# IO_Expander.net
KiCad netlist of a schematic drawn in Altium Designer
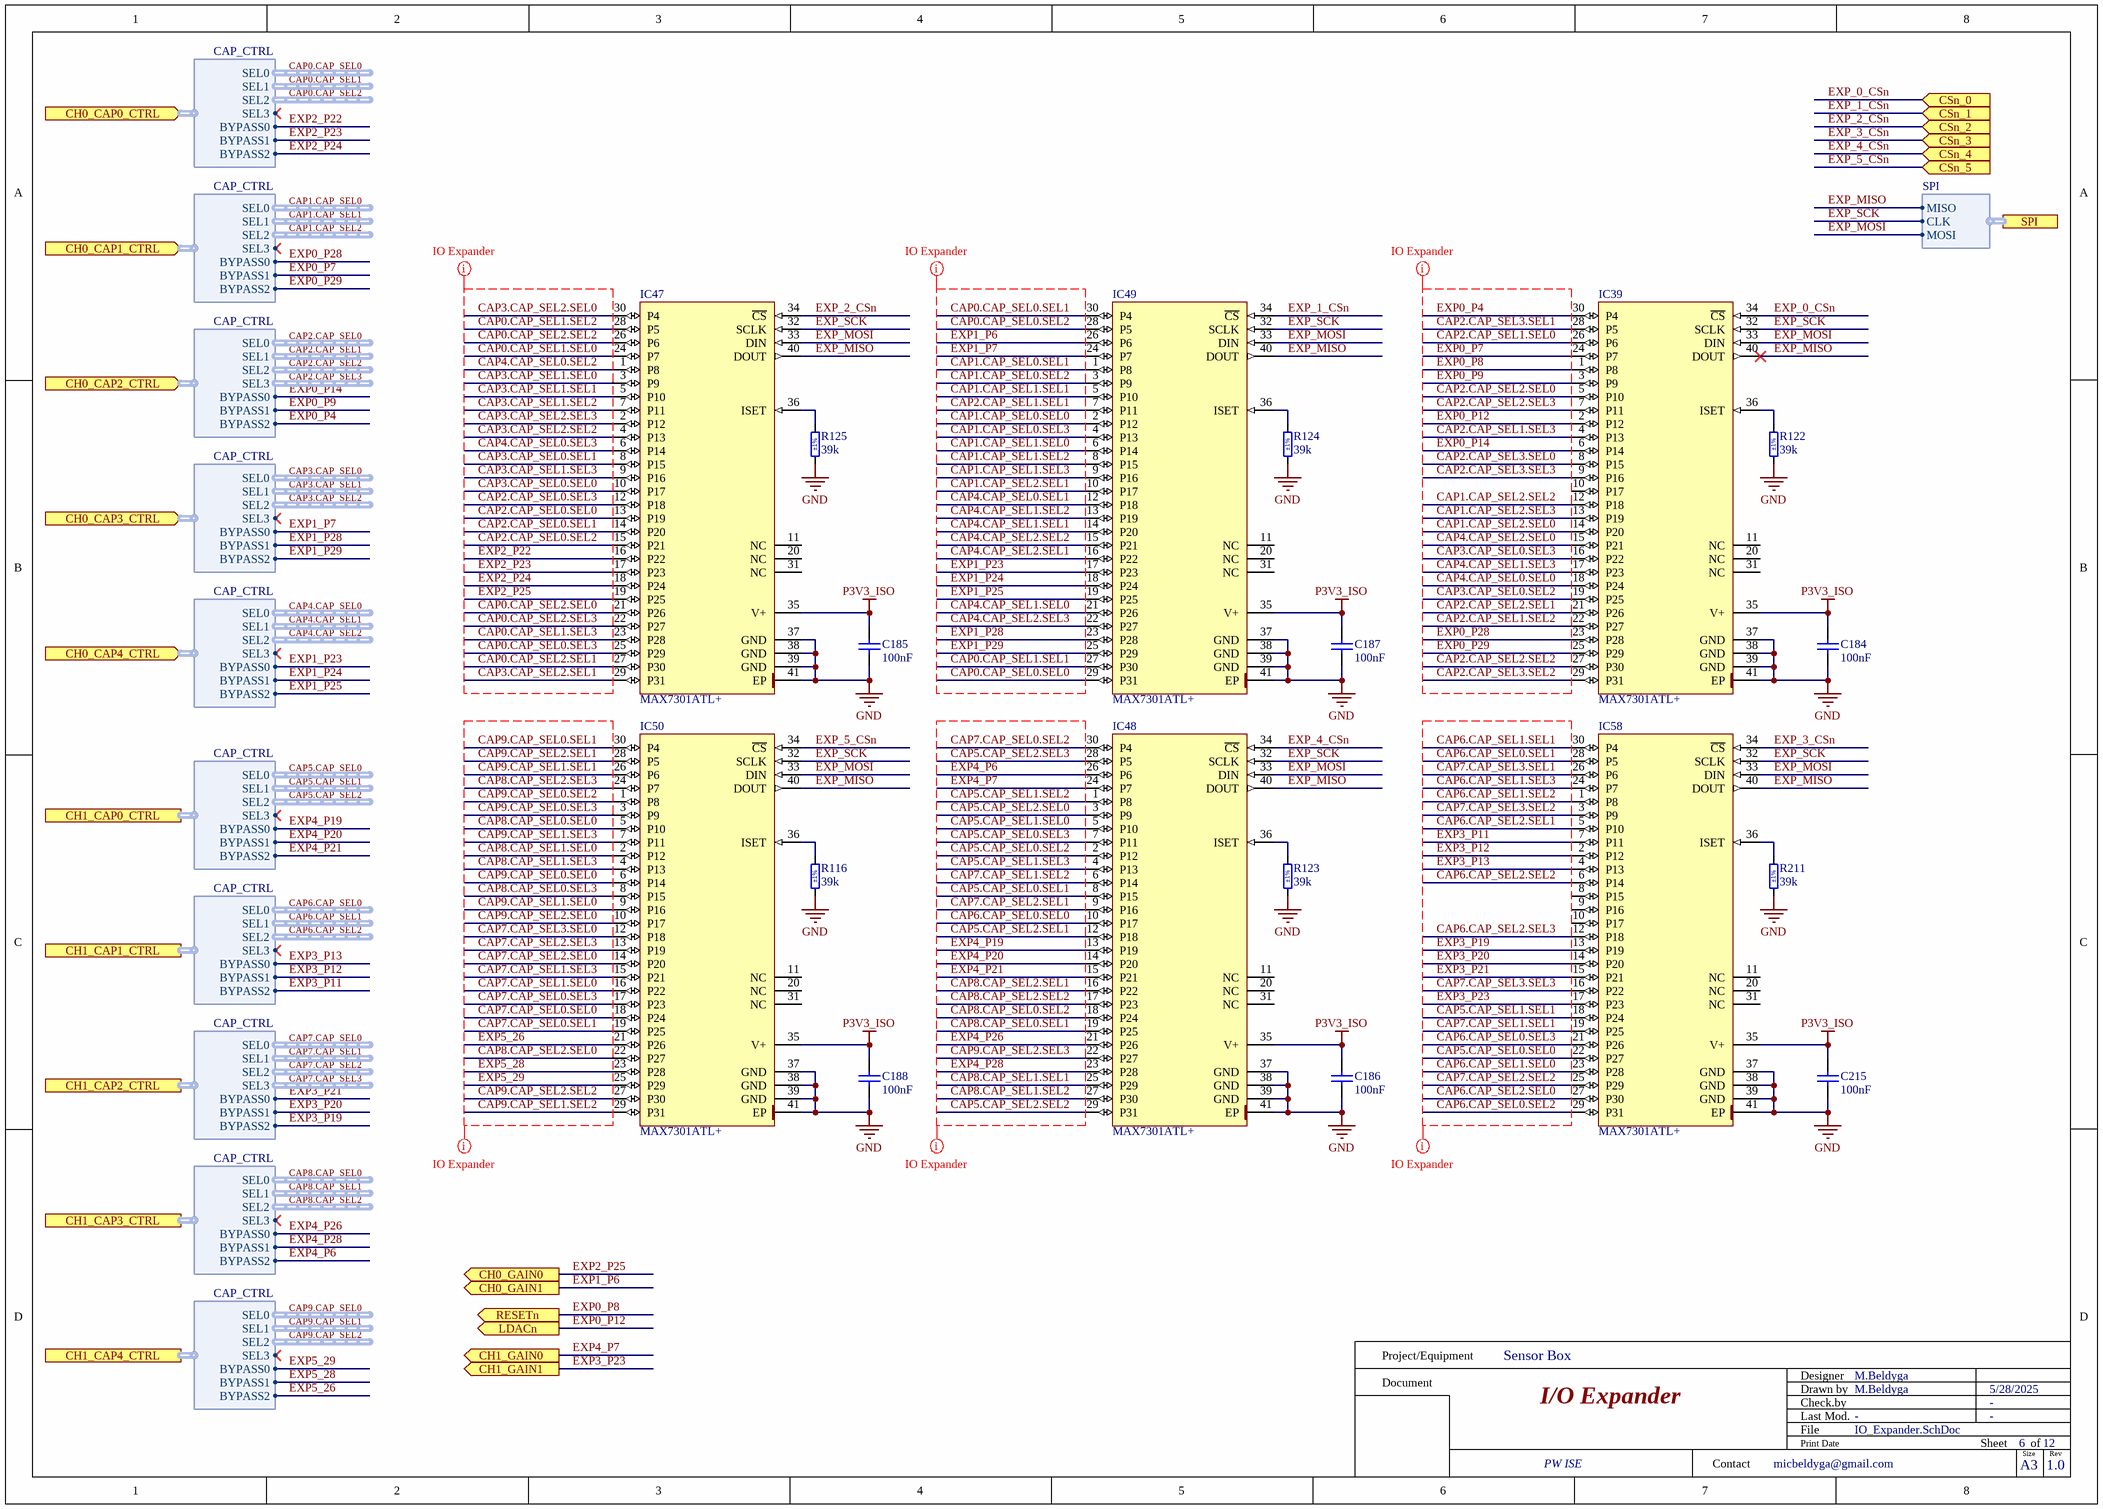
[diagram p0: IO_Expander.SchDoc]

(export (version "E")
  (design (tool "Eeschema 10.0.6"))
  (components
    (comp (ref "C184")
      (value "100nF")
      (footprint "CAPC1005X55N")
      (description "Non-polarised capacitor")
      (fields
        (field (name "PART NUMBER") "CC0402_100NF_50V_10%_X7R")
        (field (name "VOLTAGE") "50V")
        (field (name "AUTHOR") "CERN DEM MR")
      )
      (libsource (lib "Capacitors") (part "Capacitor - non polarized"))
    )
    (comp (ref "C185")
      (value "100nF")
      (footprint "CAPC1005X55N")
      (description "Non-polarised capacitor")
      (fields
        (field (name "PART NUMBER") "CC0402_100NF_50V_10%_X7R")
        (field (name "VOLTAGE") "50V")
        (field (name "AUTHOR") "CERN DEM MR")
      )
      (libsource (lib "Capacitors") (part "Capacitor - non polarized"))
    )
    (comp (ref "C186")
      (value "100nF")
      (footprint "CAPC1005X55N")
      (description "Non-polarised capacitor")
      (fields
        (field (name "PART NUMBER") "CC0402_100NF_50V_10%_X7R")
        (field (name "VOLTAGE") "50V")
        (field (name "AUTHOR") "CERN DEM MR")
      )
      (libsource (lib "Capacitors") (part "Capacitor - non polarized"))
    )
    (comp (ref "C187")
      (value "100nF")
      (footprint "CAPC1005X55N")
      (description "Non-polarised capacitor")
      (fields
        (field (name "PART NUMBER") "CC0402_100NF_50V_10%_X7R")
        (field (name "VOLTAGE") "50V")
        (field (name "AUTHOR") "CERN DEM MR")
      )
      (libsource (lib "Capacitors") (part "Capacitor - non polarized"))
    )
    (comp (ref "C188")
      (value "100nF")
      (footprint "CAPC1005X55N")
      (description "Non-polarised capacitor")
      (fields
        (field (name "PART NUMBER") "CC0402_100NF_50V_10%_X7R")
        (field (name "VOLTAGE") "50V")
        (field (name "AUTHOR") "CERN DEM MR")
      )
      (libsource (lib "Capacitors") (part "Capacitor - non polarized"))
    )
    (comp (ref "C215")
      (value "100nF")
      (footprint "CAPC1005X55N")
      (description "Non-polarised capacitor")
      (fields
        (field (name "PART NUMBER") "CC0402_100NF_50V_10%_X7R")
        (field (name "VOLTAGE") "50V")
        (field (name "AUTHOR") "CERN DEM MR")
      )
      (libsource (lib "Capacitors") (part "Capacitor - non polarized"))
    )
    (comp (ref "IC39")
      (value "MAX7301ATL+")
      (footprint "QFN50P600X600X80-41N-S425")
      (description "4-Wire-Interfaced, 2.5V to 5.5V, 28-Port I/O Expander")
      (fields
        (field (name "MANUFACTURER") "MAXIM")
        (field (name "MANUFACTURER PART NUMBER") "MAX7301ATL")
        (field (name "AUTHOR") "CERN DEM BC")
      )
      (libsource (lib "ICs And Semiconductors") (part "MAX7301ATL+"))
    )
    (comp (ref "IC47")
      (value "MAX7301ATL+")
      (footprint "QFN50P600X600X80-41N-S425")
      (description "4-Wire-Interfaced, 2.5V to 5.5V, 28-Port I/O Expander")
      (fields
        (field (name "MANUFACTURER") "MAXIM")
        (field (name "MANUFACTURER PART NUMBER") "MAX7301ATL")
        (field (name "AUTHOR") "CERN DEM BC")
      )
      (libsource (lib "ICs And Semiconductors") (part "MAX7301ATL+"))
    )
    (comp (ref "IC48")
      (value "MAX7301ATL+")
      (footprint "QFN50P600X600X80-41N-S425")
      (description "4-Wire-Interfaced, 2.5V to 5.5V, 28-Port I/O Expander")
      (fields
        (field (name "MANUFACTURER") "MAXIM")
        (field (name "MANUFACTURER PART NUMBER") "MAX7301ATL")
        (field (name "AUTHOR") "CERN DEM BC")
      )
      (libsource (lib "ICs And Semiconductors") (part "MAX7301ATL+"))
    )
    (comp (ref "IC49")
      (value "MAX7301ATL+")
      (footprint "QFN50P600X600X80-41N-S425")
      (description "4-Wire-Interfaced, 2.5V to 5.5V, 28-Port I/O Expander")
      (fields
        (field (name "MANUFACTURER") "MAXIM")
        (field (name "MANUFACTURER PART NUMBER") "MAX7301ATL")
        (field (name "AUTHOR") "CERN DEM BC")
      )
      (libsource (lib "ICs And Semiconductors") (part "MAX7301ATL+"))
    )
    (comp (ref "IC50")
      (value "MAX7301ATL+")
      (footprint "QFN50P600X600X80-41N-S425")
      (description "4-Wire-Interfaced, 2.5V to 5.5V, 28-Port I/O Expander")
      (fields
        (field (name "MANUFACTURER") "MAXIM")
        (field (name "MANUFACTURER PART NUMBER") "MAX7301ATL")
        (field (name "AUTHOR") "CERN DEM BC")
      )
      (libsource (lib "ICs And Semiconductors") (part "MAX7301ATL+"))
    )
    (comp (ref "IC58")
      (value "MAX7301ATL+")
      (footprint "QFN50P600X600X80-41N-S425")
      (description "4-Wire-Interfaced, 2.5V to 5.5V, 28-Port I/O Expander")
      (fields
        (field (name "MANUFACTURER") "MAXIM")
        (field (name "MANUFACTURER PART NUMBER") "MAX7301ATL")
        (field (name "AUTHOR") "CERN DEM BC")
      )
      (libsource (lib "ICs And Semiconductors") (part "MAX7301ATL+"))
    )
    (comp (ref "R116")
      (value "39k")
      (footprint "RESC1005X40N")
      (description "Resistor - 1%")
      (fields
        (field (name "TOLERANCE") "±1%")
        (field (name "PART NUMBER") "R0402_39K_1%_0.0625W_100PPM")
        (field (name "POWER") "0.0625W")
        (field (name "AUTHOR") "CERN DEM JLC")
      )
      (libsource (lib "Resistors") (part "Resistor - 1%"))
    )
    (comp (ref "R122")
      (value "39k")
      (footprint "RESC1005X40N")
      (description "Resistor - 1%")
      (fields
        (field (name "TOLERANCE") "±1%")
        (field (name "PART NUMBER") "R0402_39K_1%_0.0625W_100PPM")
        (field (name "POWER") "0.0625W")
        (field (name "AUTHOR") "CERN DEM JLC")
      )
      (libsource (lib "Resistors") (part "Resistor - 1%"))
    )
    (comp (ref "R123")
      (value "39k")
      (footprint "RESC1005X40N")
      (description "Resistor - 1%")
      (fields
        (field (name "TOLERANCE") "±1%")
        (field (name "PART NUMBER") "R0402_39K_1%_0.0625W_100PPM")
        (field (name "POWER") "0.0625W")
        (field (name "AUTHOR") "CERN DEM JLC")
      )
      (libsource (lib "Resistors") (part "Resistor - 1%"))
    )
    (comp (ref "R124")
      (value "39k")
      (footprint "RESC1005X40N")
      (description "Resistor - 1%")
      (fields
        (field (name "TOLERANCE") "±1%")
        (field (name "PART NUMBER") "R0402_39K_1%_0.0625W_100PPM")
        (field (name "POWER") "0.0625W")
        (field (name "AUTHOR") "CERN DEM JLC")
      )
      (libsource (lib "Resistors") (part "Resistor - 1%"))
    )
    (comp (ref "R125")
      (value "39k")
      (footprint "RESC1005X40N")
      (description "Resistor - 1%")
      (fields
        (field (name "TOLERANCE") "±1%")
        (field (name "PART NUMBER") "R0402_39K_1%_0.0625W_100PPM")
        (field (name "POWER") "0.0625W")
        (field (name "AUTHOR") "CERN DEM JLC")
      )
      (libsource (lib "Resistors") (part "Resistor - 1%"))
    )
    (comp (ref "R211")
      (value "39k")
      (footprint "RESC1005X40N")
      (description "Resistor - 1%")
      (fields
        (field (name "TOLERANCE") "±1%")
        (field (name "PART NUMBER") "R0402_39K_1%_0.0625W_100PPM")
        (field (name "POWER") "0.0625W")
        (field (name "AUTHOR") "CERN DEM JLC")
      )
      (libsource (lib "Resistors") (part "Resistor - 1%"))
    )
  )
  (nets
    (net (code "39") (name "/CAP0.CAP_SEL0.SEL0") (class "Default")
      (node (ref "IC49") (pin "29") (pinfunction "P31_29") (pintype "bidirectional"))
    )
    (net (code "40") (name "/CAP0.CAP_SEL0.SEL1") (class "Default")
      (node (ref "IC49") (pin "30") (pinfunction "P4_30") (pintype "bidirectional"))
    )
    (net (code "41") (name "/CAP0.CAP_SEL0.SEL2") (class "Default")
      (node (ref "IC49") (pin "28") (pinfunction "P5_28") (pintype "bidirectional"))
    )
    (net (code "42") (name "/CAP0.CAP_SEL0.SEL3") (class "Default")
      (node (ref "IC47") (pin "25") (pinfunction "P29_25") (pintype "bidirectional"))
    )
    (net (code "43") (name "/CAP0.CAP_SEL1.SEL0") (class "Default")
      (node (ref "IC47") (pin "24") (pinfunction "P7_24") (pintype "bidirectional"))
    )
    (net (code "44") (name "/CAP0.CAP_SEL1.SEL1") (class "Default")
      (node (ref "IC49") (pin "27") (pinfunction "P30_27") (pintype "bidirectional"))
    )
    (net (code "45") (name "/CAP0.CAP_SEL1.SEL2") (class "Default")
      (node (ref "IC47") (pin "28") (pinfunction "P5_28") (pintype "bidirectional"))
    )
    (net (code "46") (name "/CAP0.CAP_SEL1.SEL3") (class "Default")
      (node (ref "IC47") (pin "23") (pinfunction "P28_23") (pintype "bidirectional"))
    )
    (net (code "47") (name "/CAP0.CAP_SEL2.SEL0") (class "Default")
      (node (ref "IC47") (pin "21") (pinfunction "P26_21") (pintype "bidirectional"))
    )
    (net (code "48") (name "/CAP0.CAP_SEL2.SEL1") (class "Default")
      (node (ref "IC47") (pin "27") (pinfunction "P30_27") (pintype "bidirectional"))
    )
    (net (code "49") (name "/CAP0.CAP_SEL2.SEL2") (class "Default")
      (node (ref "IC47") (pin "26") (pinfunction "P6_26") (pintype "bidirectional"))
    )
    (net (code "50") (name "/CAP0.CAP_SEL2.SEL3") (class "Default")
      (node (ref "IC47") (pin "22") (pinfunction "P27_22") (pintype "bidirectional"))
    )
    (net (code "51") (name "/CAP1.CAP_SEL0.SEL0") (class "Default")
      (node (ref "IC49") (pin "2") (pinfunction "P12_2") (pintype "bidirectional"))
    )
    (net (code "52") (name "/CAP1.CAP_SEL0.SEL1") (class "Default")
      (node (ref "IC49") (pin "1") (pinfunction "P8_1") (pintype "bidirectional"))
    )
    (net (code "53") (name "/CAP1.CAP_SEL0.SEL2") (class "Default")
      (node (ref "IC49") (pin "3") (pinfunction "P9_3") (pintype "bidirectional"))
    )
    (net (code "54") (name "/CAP1.CAP_SEL0.SEL3") (class "Default")
      (node (ref "IC49") (pin "4") (pinfunction "P13_4") (pintype "bidirectional"))
    )
    (net (code "55") (name "/CAP1.CAP_SEL1.SEL0") (class "Default")
      (node (ref "IC49") (pin "6") (pinfunction "P14_6") (pintype "bidirectional"))
    )
    (net (code "56") (name "/CAP1.CAP_SEL1.SEL1") (class "Default")
      (node (ref "IC49") (pin "5") (pinfunction "P10_5") (pintype "bidirectional"))
    )
    (net (code "57") (name "/CAP1.CAP_SEL1.SEL2") (class "Default")
      (node (ref "IC49") (pin "8") (pinfunction "P15_8") (pintype "bidirectional"))
    )
    (net (code "58") (name "/CAP1.CAP_SEL1.SEL3") (class "Default")
      (node (ref "IC49") (pin "9") (pinfunction "P16_9") (pintype "bidirectional"))
    )
    (net (code "59") (name "/CAP1.CAP_SEL2.SEL0") (class "Default")
      (node (ref "IC39") (pin "14") (pinfunction "P20_14") (pintype "bidirectional"))
    )
    (net (code "60") (name "/CAP1.CAP_SEL2.SEL1") (class "Default")
      (node (ref "IC49") (pin "10") (pinfunction "P17_10") (pintype "bidirectional"))
    )
    (net (code "61") (name "/CAP1.CAP_SEL2.SEL2") (class "Default")
      (node (ref "IC39") (pin "12") (pinfunction "P18_12") (pintype "bidirectional"))
    )
    (net (code "62") (name "/CAP1.CAP_SEL2.SEL3") (class "Default")
      (node (ref "IC39") (pin "13") (pinfunction "P19_13") (pintype "bidirectional"))
    )
    (net (code "63") (name "/CAP2.CAP_SEL0.SEL0") (class "Default")
      (node (ref "IC47") (pin "13") (pinfunction "P19_13") (pintype "bidirectional"))
    )
    (net (code "64") (name "/CAP2.CAP_SEL0.SEL1") (class "Default")
      (node (ref "IC47") (pin "14") (pinfunction "P20_14") (pintype "bidirectional"))
    )
    (net (code "65") (name "/CAP2.CAP_SEL0.SEL2") (class "Default")
      (node (ref "IC47") (pin "15") (pinfunction "P21_15") (pintype "bidirectional"))
    )
    (net (code "66") (name "/CAP2.CAP_SEL0.SEL3") (class "Default")
      (node (ref "IC47") (pin "12") (pinfunction "P18_12") (pintype "bidirectional"))
    )
    (net (code "67") (name "/CAP2.CAP_SEL1.SEL0") (class "Default")
      (node (ref "IC39") (pin "26") (pinfunction "P6_26") (pintype "bidirectional"))
    )
    (net (code "68") (name "/CAP2.CAP_SEL1.SEL1") (class "Default")
      (node (ref "IC49") (pin "7") (pinfunction "P11_7") (pintype "bidirectional"))
    )
    (net (code "69") (name "/CAP2.CAP_SEL1.SEL2") (class "Default")
      (node (ref "IC39") (pin "22") (pinfunction "P27_22") (pintype "bidirectional"))
    )
    (net (code "70") (name "/CAP2.CAP_SEL1.SEL3") (class "Default")
      (node (ref "IC39") (pin "4") (pinfunction "P13_4") (pintype "bidirectional"))
    )
    (net (code "71") (name "/CAP2.CAP_SEL2.SEL0") (class "Default")
      (node (ref "IC39") (pin "5") (pinfunction "P10_5") (pintype "bidirectional"))
    )
    (net (code "72") (name "/CAP2.CAP_SEL2.SEL1") (class "Default")
      (node (ref "IC39") (pin "21") (pinfunction "P26_21") (pintype "bidirectional"))
    )
    (net (code "73") (name "/CAP2.CAP_SEL2.SEL2") (class "Default")
      (node (ref "IC39") (pin "27") (pinfunction "P30_27") (pintype "bidirectional"))
    )
    (net (code "74") (name "/CAP2.CAP_SEL2.SEL3") (class "Default")
      (node (ref "IC39") (pin "7") (pinfunction "P11_7") (pintype "bidirectional"))
    )
    (net (code "75") (name "/CAP2.CAP_SEL3.SEL0") (class "Default")
      (node (ref "IC39") (pin "8") (pinfunction "P15_8") (pintype "bidirectional"))
    )
    (net (code "76") (name "/CAP2.CAP_SEL3.SEL1") (class "Default")
      (node (ref "IC39") (pin "28") (pinfunction "P5_28") (pintype "bidirectional"))
    )
    (net (code "77") (name "/CAP2.CAP_SEL3.SEL2") (class "Default")
      (node (ref "IC39") (pin "29") (pinfunction "P31_29") (pintype "bidirectional"))
    )
    (net (code "78") (name "/CAP2.CAP_SEL3.SEL3") (class "Default")
      (node (ref "IC39") (pin "9") (pinfunction "P16_9") (pintype "bidirectional"))
    )
    (net (code "80") (name "/CAP3.CAP_SEL0.SEL0") (class "Default")
      (node (ref "IC47") (pin "10") (pinfunction "P17_10") (pintype "bidirectional"))
    )
    (net (code "81") (name "/CAP3.CAP_SEL0.SEL1") (class "Default")
      (node (ref "IC47") (pin "8") (pinfunction "P15_8") (pintype "bidirectional"))
    )
    (net (code "82") (name "/CAP3.CAP_SEL0.SEL2") (class "Default")
      (node (ref "IC39") (pin "19") (pinfunction "P25_19") (pintype "bidirectional"))
    )
    (net (code "83") (name "/CAP3.CAP_SEL0.SEL3") (class "Default")
      (node (ref "IC39") (pin "16") (pinfunction "P22_16") (pintype "bidirectional"))
    )
    (net (code "84") (name "/CAP3.CAP_SEL1.SEL0") (class "Default")
      (node (ref "IC47") (pin "3") (pinfunction "P9_3") (pintype "bidirectional"))
    )
    (net (code "85") (name "/CAP3.CAP_SEL1.SEL1") (class "Default")
      (node (ref "IC47") (pin "5") (pinfunction "P10_5") (pintype "bidirectional"))
    )
    (net (code "86") (name "/CAP3.CAP_SEL1.SEL2") (class "Default")
      (node (ref "IC47") (pin "7") (pinfunction "P11_7") (pintype "bidirectional"))
    )
    (net (code "87") (name "/CAP3.CAP_SEL1.SEL3") (class "Default")
      (node (ref "IC47") (pin "9") (pinfunction "P16_9") (pintype "bidirectional"))
    )
    (net (code "88") (name "/CAP3.CAP_SEL2.SEL0") (class "Default")
      (node (ref "IC47") (pin "30") (pinfunction "P4_30") (pintype "bidirectional"))
    )
    (net (code "89") (name "/CAP3.CAP_SEL2.SEL1") (class "Default")
      (node (ref "IC47") (pin "29") (pinfunction "P31_29") (pintype "bidirectional"))
    )
    (net (code "90") (name "/CAP3.CAP_SEL2.SEL2") (class "Default")
      (node (ref "IC47") (pin "4") (pinfunction "P13_4") (pintype "bidirectional"))
    )
    (net (code "91") (name "/CAP3.CAP_SEL2.SEL3") (class "Default")
      (node (ref "IC47") (pin "2") (pinfunction "P12_2") (pintype "bidirectional"))
    )
    (net (code "92") (name "/CAP4.CAP_SEL0.SEL0") (class "Default")
      (node (ref "IC39") (pin "18") (pinfunction "P24_18") (pintype "bidirectional"))
    )
    (net (code "93") (name "/CAP4.CAP_SEL0.SEL1") (class "Default")
      (node (ref "IC49") (pin "12") (pinfunction "P18_12") (pintype "bidirectional"))
    )
    (net (code "94") (name "/CAP4.CAP_SEL0.SEL2") (class "Default")
      (node (ref "IC47") (pin "1") (pinfunction "P8_1") (pintype "bidirectional"))
    )
    (net (code "95") (name "/CAP4.CAP_SEL0.SEL3") (class "Default")
      (node (ref "IC47") (pin "6") (pinfunction "P14_6") (pintype "bidirectional"))
    )
    (net (code "96") (name "/CAP4.CAP_SEL1.SEL0") (class "Default")
      (node (ref "IC49") (pin "21") (pinfunction "P26_21") (pintype "bidirectional"))
    )
    (net (code "97") (name "/CAP4.CAP_SEL1.SEL1") (class "Default")
      (node (ref "IC49") (pin "14") (pinfunction "P20_14") (pintype "bidirectional"))
    )
    (net (code "98") (name "/CAP4.CAP_SEL1.SEL2") (class "Default")
      (node (ref "IC49") (pin "13") (pinfunction "P19_13") (pintype "bidirectional"))
    )
    (net (code "99") (name "/CAP4.CAP_SEL1.SEL3") (class "Default")
      (node (ref "IC39") (pin "17") (pinfunction "P23_17") (pintype "bidirectional"))
    )
    (net (code "100") (name "/CAP4.CAP_SEL2.SEL0") (class "Default")
      (node (ref "IC39") (pin "15") (pinfunction "P21_15") (pintype "bidirectional"))
    )
    (net (code "101") (name "/CAP4.CAP_SEL2.SEL1") (class "Default")
      (node (ref "IC49") (pin "16") (pinfunction "P22_16") (pintype "bidirectional"))
    )
    (net (code "102") (name "/CAP4.CAP_SEL2.SEL2") (class "Default")
      (node (ref "IC49") (pin "15") (pinfunction "P21_15") (pintype "bidirectional"))
    )
    (net (code "103") (name "/CAP4.CAP_SEL2.SEL3") (class "Default")
      (node (ref "IC49") (pin "22") (pinfunction "P27_22") (pintype "bidirectional"))
    )
    (net (code "104") (name "/CAP5.CAP_SEL0.SEL0") (class "Default")
      (node (ref "IC58") (pin "22") (pinfunction "P27_22") (pintype "bidirectional"))
    )
    (net (code "105") (name "/CAP5.CAP_SEL0.SEL1") (class "Default")
      (node (ref "IC48") (pin "8") (pinfunction "P15_8") (pintype "bidirectional"))
    )
    (net (code "106") (name "/CAP5.CAP_SEL0.SEL2") (class "Default")
      (node (ref "IC48") (pin "2") (pinfunction "P12_2") (pintype "bidirectional"))
    )
    (net (code "107") (name "/CAP5.CAP_SEL0.SEL3") (class "Default")
      (node (ref "IC48") (pin "7") (pinfunction "P11_7") (pintype "bidirectional"))
    )
    (net (code "108") (name "/CAP5.CAP_SEL1.SEL0") (class "Default")
      (node (ref "IC48") (pin "5") (pinfunction "P10_5") (pintype "bidirectional"))
    )
    (net (code "109") (name "/CAP5.CAP_SEL1.SEL1") (class "Default")
      (node (ref "IC58") (pin "18") (pinfunction "P24_18") (pintype "bidirectional"))
    )
    (net (code "110") (name "/CAP5.CAP_SEL1.SEL2") (class "Default")
      (node (ref "IC48") (pin "1") (pinfunction "P8_1") (pintype "bidirectional"))
    )
    (net (code "111") (name "/CAP5.CAP_SEL1.SEL3") (class "Default")
      (node (ref "IC48") (pin "4") (pinfunction "P13_4") (pintype "bidirectional"))
    )
    (net (code "112") (name "/CAP5.CAP_SEL2.SEL0") (class "Default")
      (node (ref "IC48") (pin "3") (pinfunction "P9_3") (pintype "bidirectional"))
    )
    (net (code "113") (name "/CAP5.CAP_SEL2.SEL1") (class "Default")
      (node (ref "IC48") (pin "12") (pinfunction "P18_12") (pintype "bidirectional"))
    )
    (net (code "114") (name "/CAP5.CAP_SEL2.SEL2") (class "Default")
      (node (ref "IC48") (pin "29") (pinfunction "P31_29") (pintype "bidirectional"))
    )
    (net (code "115") (name "/CAP5.CAP_SEL2.SEL3") (class "Default")
      (node (ref "IC48") (pin "28") (pinfunction "P5_28") (pintype "bidirectional"))
    )
    (net (code "117") (name "/CAP6.CAP_SEL0.SEL0") (class "Default")
      (node (ref "IC48") (pin "10") (pinfunction "P17_10") (pintype "bidirectional"))
    )
    (net (code "118") (name "/CAP6.CAP_SEL0.SEL1") (class "Default")
      (node (ref "IC58") (pin "28") (pinfunction "P5_28") (pintype "bidirectional"))
    )
    (net (code "119") (name "/CAP6.CAP_SEL0.SEL2") (class "Default")
      (node (ref "IC58") (pin "29") (pinfunction "P31_29") (pintype "bidirectional"))
    )
    (net (code "120") (name "/CAP6.CAP_SEL0.SEL3") (class "Default")
      (node (ref "IC58") (pin "21") (pinfunction "P26_21") (pintype "bidirectional"))
    )
    (net (code "121") (name "/CAP6.CAP_SEL1.SEL0") (class "Default")
      (node (ref "IC58") (pin "23") (pinfunction "P28_23") (pintype "bidirectional"))
    )
    (net (code "122") (name "/CAP6.CAP_SEL1.SEL1") (class "Default")
      (node (ref "IC58") (pin "30") (pinfunction "P4_30") (pintype "bidirectional"))
    )
    (net (code "123") (name "/CAP6.CAP_SEL1.SEL2") (class "Default")
      (node (ref "IC58") (pin "1") (pinfunction "P8_1") (pintype "bidirectional"))
    )
    (net (code "124") (name "/CAP6.CAP_SEL1.SEL3") (class "Default")
      (node (ref "IC58") (pin "24") (pinfunction "P7_24") (pintype "bidirectional"))
    )
    (net (code "125") (name "/CAP6.CAP_SEL2.SEL0") (class "Default")
      (node (ref "IC58") (pin "27") (pinfunction "P30_27") (pintype "bidirectional"))
    )
    (net (code "126") (name "/CAP6.CAP_SEL2.SEL1") (class "Default")
      (node (ref "IC58") (pin "5") (pinfunction "P10_5") (pintype "bidirectional"))
    )
    (net (code "127") (name "/CAP6.CAP_SEL2.SEL2") (class "Default")
      (node (ref "IC58") (pin "6") (pinfunction "P14_6") (pintype "bidirectional"))
    )
    (net (code "128") (name "/CAP6.CAP_SEL2.SEL3") (class "Default")
      (node (ref "IC58") (pin "12") (pinfunction "P18_12") (pintype "bidirectional"))
    )
    (net (code "130") (name "/CAP7.CAP_SEL0.SEL0") (class "Default")
      (node (ref "IC50") (pin "18") (pinfunction "P24_18") (pintype "bidirectional"))
    )
    (net (code "131") (name "/CAP7.CAP_SEL0.SEL1") (class "Default")
      (node (ref "IC50") (pin "19") (pinfunction "P25_19") (pintype "bidirectional"))
    )
    (net (code "132") (name "/CAP7.CAP_SEL0.SEL2") (class "Default")
      (node (ref "IC48") (pin "30") (pinfunction "P4_30") (pintype "bidirectional"))
    )
    (net (code "133") (name "/CAP7.CAP_SEL0.SEL3") (class "Default")
      (node (ref "IC50") (pin "17") (pinfunction "P23_17") (pintype "bidirectional"))
    )
    (net (code "134") (name "/CAP7.CAP_SEL1.SEL0") (class "Default")
      (node (ref "IC50") (pin "16") (pinfunction "P22_16") (pintype "bidirectional"))
    )
    (net (code "135") (name "/CAP7.CAP_SEL1.SEL1") (class "Default")
      (node (ref "IC58") (pin "19") (pinfunction "P25_19") (pintype "bidirectional"))
    )
    (net (code "136") (name "/CAP7.CAP_SEL1.SEL2") (class "Default")
      (node (ref "IC48") (pin "6") (pinfunction "P14_6") (pintype "bidirectional"))
    )
    (net (code "137") (name "/CAP7.CAP_SEL1.SEL3") (class "Default")
      (node (ref "IC50") (pin "15") (pinfunction "P21_15") (pintype "bidirectional"))
    )
    (net (code "138") (name "/CAP7.CAP_SEL2.SEL0") (class "Default")
      (node (ref "IC50") (pin "14") (pinfunction "P20_14") (pintype "bidirectional"))
    )
    (net (code "139") (name "/CAP7.CAP_SEL2.SEL1") (class "Default")
      (node (ref "IC48") (pin "9") (pinfunction "P16_9") (pintype "bidirectional"))
    )
    (net (code "140") (name "/CAP7.CAP_SEL2.SEL2") (class "Default")
      (node (ref "IC58") (pin "25") (pinfunction "P29_25") (pintype "bidirectional"))
    )
    (net (code "141") (name "/CAP7.CAP_SEL2.SEL3") (class "Default")
      (node (ref "IC50") (pin "13") (pinfunction "P19_13") (pintype "bidirectional"))
    )
    (net (code "142") (name "/CAP7.CAP_SEL3.SEL0") (class "Default")
      (node (ref "IC50") (pin "12") (pinfunction "P18_12") (pintype "bidirectional"))
    )
    (net (code "143") (name "/CAP7.CAP_SEL3.SEL1") (class "Default")
      (node (ref "IC58") (pin "26") (pinfunction "P6_26") (pintype "bidirectional"))
    )
    (net (code "144") (name "/CAP7.CAP_SEL3.SEL2") (class "Default")
      (node (ref "IC58") (pin "3") (pinfunction "P9_3") (pintype "bidirectional"))
    )
    (net (code "145") (name "/CAP7.CAP_SEL3.SEL3") (class "Default")
      (node (ref "IC58") (pin "16") (pinfunction "P22_16") (pintype "bidirectional"))
    )
    (net (code "147") (name "/CAP8.CAP_SEL0.SEL0") (class "Default")
      (node (ref "IC50") (pin "5") (pinfunction "P10_5") (pintype "bidirectional"))
    )
    (net (code "148") (name "/CAP8.CAP_SEL0.SEL1") (class "Default")
      (node (ref "IC48") (pin "19") (pinfunction "P25_19") (pintype "bidirectional"))
    )
    (net (code "149") (name "/CAP8.CAP_SEL0.SEL2") (class "Default")
      (node (ref "IC48") (pin "18") (pinfunction "P24_18") (pintype "bidirectional"))
    )
    (net (code "150") (name "/CAP8.CAP_SEL0.SEL3") (class "Default")
      (node (ref "IC50") (pin "8") (pinfunction "P15_8") (pintype "bidirectional"))
    )
    (net (code "151") (name "/CAP8.CAP_SEL1.SEL0") (class "Default")
      (node (ref "IC50") (pin "2") (pinfunction "P12_2") (pintype "bidirectional"))
    )
    (net (code "152") (name "/CAP8.CAP_SEL1.SEL1") (class "Default")
      (node (ref "IC48") (pin "25") (pinfunction "P29_25") (pintype "bidirectional"))
    )
    (net (code "153") (name "/CAP8.CAP_SEL1.SEL2") (class "Default")
      (node (ref "IC48") (pin "27") (pinfunction "P30_27") (pintype "bidirectional"))
    )
    (net (code "154") (name "/CAP8.CAP_SEL1.SEL3") (class "Default")
      (node (ref "IC50") (pin "4") (pinfunction "P13_4") (pintype "bidirectional"))
    )
    (net (code "155") (name "/CAP8.CAP_SEL2.SEL0") (class "Default")
      (node (ref "IC50") (pin "22") (pinfunction "P27_22") (pintype "bidirectional"))
    )
    (net (code "156") (name "/CAP8.CAP_SEL2.SEL1") (class "Default")
      (node (ref "IC48") (pin "16") (pinfunction "P22_16") (pintype "bidirectional"))
    )
    (net (code "157") (name "/CAP8.CAP_SEL2.SEL2") (class "Default")
      (node (ref "IC48") (pin "17") (pinfunction "P23_17") (pintype "bidirectional"))
    )
    (net (code "158") (name "/CAP8.CAP_SEL2.SEL3") (class "Default")
      (node (ref "IC50") (pin "24") (pinfunction "P7_24") (pintype "bidirectional"))
    )
    (net (code "159") (name "/CAP9.CAP_SEL0.SEL0") (class "Default")
      (node (ref "IC50") (pin "6") (pinfunction "P14_6") (pintype "bidirectional"))
    )
    (net (code "160") (name "/CAP9.CAP_SEL0.SEL1") (class "Default")
      (node (ref "IC50") (pin "30") (pinfunction "P4_30") (pintype "bidirectional"))
    )
    (net (code "161") (name "/CAP9.CAP_SEL0.SEL2") (class "Default")
      (node (ref "IC50") (pin "1") (pinfunction "P8_1") (pintype "bidirectional"))
    )
    (net (code "162") (name "/CAP9.CAP_SEL0.SEL3") (class "Default")
      (node (ref "IC50") (pin "3") (pinfunction "P9_3") (pintype "bidirectional"))
    )
    (net (code "163") (name "/CAP9.CAP_SEL1.SEL0") (class "Default")
      (node (ref "IC50") (pin "9") (pinfunction "P16_9") (pintype "bidirectional"))
    )
    (net (code "164") (name "/CAP9.CAP_SEL1.SEL1") (class "Default")
      (node (ref "IC50") (pin "26") (pinfunction "P6_26") (pintype "bidirectional"))
    )
    (net (code "165") (name "/CAP9.CAP_SEL1.SEL2") (class "Default")
      (node (ref "IC50") (pin "29") (pinfunction "P31_29") (pintype "bidirectional"))
    )
    (net (code "166") (name "/CAP9.CAP_SEL1.SEL3") (class "Default")
      (node (ref "IC50") (pin "7") (pinfunction "P11_7") (pintype "bidirectional"))
    )
    (net (code "167") (name "/CAP9.CAP_SEL2.SEL0") (class "Default")
      (node (ref "IC50") (pin "10") (pinfunction "P17_10") (pintype "bidirectional"))
    )
    (net (code "168") (name "/CAP9.CAP_SEL2.SEL1") (class "Default")
      (node (ref "IC50") (pin "28") (pinfunction "P5_28") (pintype "bidirectional"))
    )
    (net (code "169") (name "/CAP9.CAP_SEL2.SEL2") (class "Default")
      (node (ref "IC50") (pin "27") (pinfunction "P30_27") (pintype "bidirectional"))
    )
    (net (code "170") (name "/CAP9.CAP_SEL2.SEL3") (class "Default")
      (node (ref "IC48") (pin "22") (pinfunction "P27_22") (pintype "bidirectional"))
    )
    (net (code "175") (name "/EXP0_P4") (class "Default")
      (node (ref "IC39") (pin "30") (pinfunction "P4_30") (pintype "bidirectional"))
    )
    (net (code "176") (name "/EXP0_P7") (class "Default")
      (node (ref "IC39") (pin "24") (pinfunction "P7_24") (pintype "bidirectional"))
    )
    (net (code "177") (name "/EXP0_P8") (class "Default")
      (node (ref "IC39") (pin "1") (pinfunction "P8_1") (pintype "bidirectional"))
    )
    (net (code "178") (name "/EXP0_P9") (class "Default")
      (node (ref "IC39") (pin "3") (pinfunction "P9_3") (pintype "bidirectional"))
    )
    (net (code "179") (name "/EXP0_P12") (class "Default")
      (node (ref "IC39") (pin "2") (pinfunction "P12_2") (pintype "bidirectional"))
    )
    (net (code "180") (name "/EXP0_P14") (class "Default")
      (node (ref "IC39") (pin "6") (pinfunction "P14_6") (pintype "bidirectional"))
    )
    (net (code "181") (name "/EXP0_P28") (class "Default")
      (node (ref "IC39") (pin "23") (pinfunction "P28_23") (pintype "bidirectional"))
    )
    (net (code "182") (name "/EXP0_P29") (class "Default")
      (node (ref "IC39") (pin "25") (pinfunction "P29_25") (pintype "bidirectional"))
    )
    (net (code "183") (name "/EXP1_P6") (class "Default")
      (node (ref "IC49") (pin "26") (pinfunction "P6_26") (pintype "bidirectional"))
    )
    (net (code "184") (name "/EXP1_P7") (class "Default")
      (node (ref "IC49") (pin "24") (pinfunction "P7_24") (pintype "bidirectional"))
    )
    (net (code "185") (name "/EXP1_P23") (class "Default")
      (node (ref "IC49") (pin "17") (pinfunction "P23_17") (pintype "bidirectional"))
    )
    (net (code "186") (name "/EXP1_P24") (class "Default")
      (node (ref "IC49") (pin "18") (pinfunction "P24_18") (pintype "bidirectional"))
    )
    (net (code "187") (name "/EXP1_P25") (class "Default")
      (node (ref "IC49") (pin "19") (pinfunction "P25_19") (pintype "bidirectional"))
    )
    (net (code "188") (name "/EXP1_P28") (class "Default")
      (node (ref "IC49") (pin "23") (pinfunction "P28_23") (pintype "bidirectional"))
    )
    (net (code "189") (name "/EXP1_P29") (class "Default")
      (node (ref "IC49") (pin "25") (pinfunction "P29_25") (pintype "bidirectional"))
    )
    (net (code "190") (name "/EXP2_P22") (class "Default")
      (node (ref "IC47") (pin "16") (pinfunction "P22_16") (pintype "bidirectional"))
    )
    (net (code "191") (name "/EXP2_P23") (class "Default")
      (node (ref "IC47") (pin "17") (pinfunction "P23_17") (pintype "bidirectional"))
    )
    (net (code "192") (name "/EXP2_P24") (class "Default")
      (node (ref "IC47") (pin "18") (pinfunction "P24_18") (pintype "bidirectional"))
    )
    (net (code "193") (name "/EXP2_P25") (class "Default")
      (node (ref "IC47") (pin "19") (pinfunction "P25_19") (pintype "bidirectional"))
    )
    (net (code "194") (name "/EXP3_P11") (class "Default")
      (node (ref "IC58") (pin "7") (pinfunction "P11_7") (pintype "bidirectional"))
    )
    (net (code "195") (name "/EXP3_P12") (class "Default")
      (node (ref "IC58") (pin "2") (pinfunction "P12_2") (pintype "bidirectional"))
    )
    (net (code "196") (name "/EXP3_P13") (class "Default")
      (node (ref "IC58") (pin "4") (pinfunction "P13_4") (pintype "bidirectional"))
    )
    (net (code "197") (name "/EXP3_P19") (class "Default")
      (node (ref "IC58") (pin "13") (pinfunction "P19_13") (pintype "bidirectional"))
    )
    (net (code "198") (name "/EXP3_P20") (class "Default")
      (node (ref "IC58") (pin "14") (pinfunction "P20_14") (pintype "bidirectional"))
    )
    (net (code "199") (name "/EXP3_P21") (class "Default")
      (node (ref "IC58") (pin "15") (pinfunction "P21_15") (pintype "bidirectional"))
    )
    (net (code "200") (name "/EXP3_P23") (class "Default")
      (node (ref "IC58") (pin "17") (pinfunction "P23_17") (pintype "bidirectional"))
    )
    (net (code "201") (name "/EXP4_P6") (class "Default")
      (node (ref "IC48") (pin "26") (pinfunction "P6_26") (pintype "bidirectional"))
    )
    (net (code "202") (name "/EXP4_P7") (class "Default")
      (node (ref "IC48") (pin "24") (pinfunction "P7_24") (pintype "bidirectional"))
    )
    (net (code "203") (name "/EXP4_P19") (class "Default")
      (node (ref "IC48") (pin "13") (pinfunction "P19_13") (pintype "bidirectional"))
    )
    (net (code "204") (name "/EXP4_P20") (class "Default")
      (node (ref "IC48") (pin "14") (pinfunction "P20_14") (pintype "bidirectional"))
    )
    (net (code "205") (name "/EXP4_P21") (class "Default")
      (node (ref "IC48") (pin "15") (pinfunction "P21_15") (pintype "bidirectional"))
    )
    (net (code "206") (name "/EXP4_P26") (class "Default")
      (node (ref "IC48") (pin "21") (pinfunction "P26_21") (pintype "bidirectional"))
    )
    (net (code "207") (name "/EXP4_P28") (class "Default")
      (node (ref "IC48") (pin "23") (pinfunction "P28_23") (pintype "bidirectional"))
    )
    (net (code "208") (name "/EXP5_26") (class "Default")
      (node (ref "IC50") (pin "21") (pinfunction "P26_21") (pintype "bidirectional"))
    )
    (net (code "209") (name "/EXP5_28") (class "Default")
      (node (ref "IC50") (pin "23") (pinfunction "P28_23") (pintype "bidirectional"))
    )
    (net (code "210") (name "/EXP5_29") (class "Default")
      (node (ref "IC50") (pin "25") (pinfunction "P29_25") (pintype "bidirectional"))
    )
    (net (code "211") (name "/EXP_0_CSn") (class "Default")
      (node (ref "IC39") (pin "34") (pinfunction "~{CS}_34") (pintype "input"))
    )
    (net (code "212") (name "/EXP_1_CSn") (class "Default")
      (node (ref "IC49") (pin "34") (pinfunction "~{CS}_34") (pintype "input"))
    )
    (net (code "213") (name "/EXP_2_CSn") (class "Default")
      (node (ref "IC47") (pin "34") (pinfunction "~{CS}_34") (pintype "input"))
    )
    (net (code "214") (name "/EXP_3_CSn") (class "Default")
      (node (ref "IC58") (pin "34") (pinfunction "~{CS}_34") (pintype "input"))
    )
    (net (code "215") (name "/EXP_4_CSn") (class "Default")
      (node (ref "IC48") (pin "34") (pinfunction "~{CS}_34") (pintype "input"))
    )
    (net (code "216") (name "/EXP_5_CSn") (class "Default")
      (node (ref "IC50") (pin "34") (pinfunction "~{CS}_34") (pintype "input"))
    )
    (net (code "217") (name "/EXP_MISO") (class "Default")
      (node (ref "IC39") (pin "40") (pinfunction "DOUT_40") (pintype "output"))
      (node (ref "IC47") (pin "40") (pinfunction "DOUT_40") (pintype "output"))
      (node (ref "IC48") (pin "40") (pinfunction "DOUT_40") (pintype "output"))
      (node (ref "IC49") (pin "40") (pinfunction "DOUT_40") (pintype "output"))
      (node (ref "IC50") (pin "40") (pinfunction "DOUT_40") (pintype "output"))
      (node (ref "IC58") (pin "40") (pinfunction "DOUT_40") (pintype "output"))
    )
    (net (code "218") (name "/EXP_MOSI") (class "Default")
      (node (ref "IC39") (pin "33") (pinfunction "DIN_33") (pintype "input"))
      (node (ref "IC47") (pin "33") (pinfunction "DIN_33") (pintype "input"))
      (node (ref "IC48") (pin "33") (pinfunction "DIN_33") (pintype "input"))
      (node (ref "IC49") (pin "33") (pinfunction "DIN_33") (pintype "input"))
      (node (ref "IC50") (pin "33") (pinfunction "DIN_33") (pintype "input"))
      (node (ref "IC58") (pin "33") (pinfunction "DIN_33") (pintype "input"))
    )
    (net (code "219") (name "/EXP_SCK") (class "Default")
      (node (ref "IC39") (pin "32") (pinfunction "SCLK_32") (pintype "input"))
      (node (ref "IC47") (pin "32") (pinfunction "SCLK_32") (pintype "input"))
      (node (ref "IC48") (pin "32") (pinfunction "SCLK_32") (pintype "input"))
      (node (ref "IC49") (pin "32") (pinfunction "SCLK_32") (pintype "input"))
      (node (ref "IC50") (pin "32") (pinfunction "SCLK_32") (pintype "input"))
      (node (ref "IC58") (pin "32") (pinfunction "SCLK_32") (pintype "input"))
    )
    (net (code "250") (name "GND") (class "Default")
      (node (ref "C184") (pin "1") (pinfunction "1_1") (pintype "passive"))
      (node (ref "C185") (pin "1") (pinfunction "1_1") (pintype "passive"))
      (node (ref "C186") (pin "1") (pinfunction "1_1") (pintype "passive"))
      (node (ref "C187") (pin "1") (pinfunction "1_1") (pintype "passive"))
      (node (ref "C188") (pin "1") (pinfunction "1_1") (pintype "passive"))
      (node (ref "C215") (pin "1") (pinfunction "1_1") (pintype "passive"))
      (node (ref "IC39") (pin "37") (pinfunction "GND_37") (pintype "power_in"))
      (node (ref "IC39") (pin "38") (pinfunction "GND_38") (pintype "power_in"))
      (node (ref "IC39") (pin "39") (pinfunction "GND_39") (pintype "power_in"))
      (node (ref "IC39") (pin "41") (pinfunction "EP_41") (pintype "power_in"))
      (node (ref "IC47") (pin "37") (pinfunction "GND_37") (pintype "power_in"))
      (node (ref "IC47") (pin "38") (pinfunction "GND_38") (pintype "power_in"))
      (node (ref "IC47") (pin "39") (pinfunction "GND_39") (pintype "power_in"))
      (node (ref "IC47") (pin "41") (pinfunction "EP_41") (pintype "power_in"))
      (node (ref "IC48") (pin "37") (pinfunction "GND_37") (pintype "power_in"))
      (node (ref "IC48") (pin "38") (pinfunction "GND_38") (pintype "power_in"))
      (node (ref "IC48") (pin "39") (pinfunction "GND_39") (pintype "power_in"))
      (node (ref "IC48") (pin "41") (pinfunction "EP_41") (pintype "power_in"))
      (node (ref "IC49") (pin "37") (pinfunction "GND_37") (pintype "power_in"))
      (node (ref "IC49") (pin "38") (pinfunction "GND_38") (pintype "power_in"))
      (node (ref "IC49") (pin "39") (pinfunction "GND_39") (pintype "power_in"))
      (node (ref "IC49") (pin "41") (pinfunction "EP_41") (pintype "power_in"))
      (node (ref "IC50") (pin "37") (pinfunction "GND_37") (pintype "power_in"))
      (node (ref "IC50") (pin "38") (pinfunction "GND_38") (pintype "power_in"))
      (node (ref "IC50") (pin "39") (pinfunction "GND_39") (pintype "power_in"))
      (node (ref "IC50") (pin "41") (pinfunction "EP_41") (pintype "power_in"))
      (node (ref "IC58") (pin "37") (pinfunction "GND_37") (pintype "power_in"))
      (node (ref "IC58") (pin "38") (pinfunction "GND_38") (pintype "power_in"))
      (node (ref "IC58") (pin "39") (pinfunction "GND_39") (pintype "power_in"))
      (node (ref "IC58") (pin "41") (pinfunction "EP_41") (pintype "power_in"))
      (node (ref "R116") (pin "1") (pinfunction "1_1") (pintype "passive"))
      (node (ref "R122") (pin "1") (pinfunction "1_1") (pintype "passive"))
      (node (ref "R123") (pin "1") (pinfunction "1_1") (pintype "passive"))
      (node (ref "R124") (pin "1") (pinfunction "1_1") (pintype "passive"))
      (node (ref "R125") (pin "1") (pinfunction "1_1") (pintype "passive"))
      (node (ref "R211") (pin "1") (pinfunction "1_1") (pintype "passive"))
    )
    (net (code "251") (name "Net-(IC39-ISET)") (class "Default")
      (node (ref "IC39") (pin "36") (pinfunction "ISET_36") (pintype "input"))
      (node (ref "R122") (pin "2") (pinfunction "2_2") (pintype "passive"))
    )
    (net (code "252") (name "Net-(IC47-ISET)") (class "Default")
      (node (ref "IC47") (pin "36") (pinfunction "ISET_36") (pintype "input"))
      (node (ref "R125") (pin "2") (pinfunction "2_2") (pintype "passive"))
    )
    (net (code "253") (name "Net-(IC48-ISET)") (class "Default")
      (node (ref "IC48") (pin "36") (pinfunction "ISET_36") (pintype "input"))
      (node (ref "R123") (pin "2") (pinfunction "2_2") (pintype "passive"))
    )
    (net (code "254") (name "Net-(IC49-ISET)") (class "Default")
      (node (ref "IC49") (pin "36") (pinfunction "ISET_36") (pintype "input"))
      (node (ref "R124") (pin "2") (pinfunction "2_2") (pintype "passive"))
    )
    (net (code "255") (name "Net-(IC50-ISET)") (class "Default")
      (node (ref "IC50") (pin "36") (pinfunction "ISET_36") (pintype "input"))
      (node (ref "R116") (pin "2") (pinfunction "2_2") (pintype "passive"))
    )
    (net (code "256") (name "Net-(IC58-ISET)") (class "Default")
      (node (ref "IC58") (pin "36") (pinfunction "ISET_36") (pintype "input"))
      (node (ref "R211") (pin "2") (pinfunction "2_2") (pintype "passive"))
    )
    (net (code "257") (name "P3V3_ISO") (class "Default")
      (node (ref "C184") (pin "2") (pinfunction "2_2") (pintype "passive"))
      (node (ref "C185") (pin "2") (pinfunction "2_2") (pintype "passive"))
      (node (ref "C186") (pin "2") (pinfunction "2_2") (pintype "passive"))
      (node (ref "C187") (pin "2") (pinfunction "2_2") (pintype "passive"))
      (node (ref "C188") (pin "2") (pinfunction "2_2") (pintype "passive"))
      (node (ref "C215") (pin "2") (pinfunction "2_2") (pintype "passive"))
      (node (ref "IC39") (pin "35") (pinfunction "V+_35") (pintype "power_in"))
      (node (ref "IC47") (pin "35") (pinfunction "V+_35") (pintype "power_in"))
      (node (ref "IC48") (pin "35") (pinfunction "V+_35") (pintype "power_in"))
      (node (ref "IC49") (pin "35") (pinfunction "V+_35") (pintype "power_in"))
      (node (ref "IC50") (pin "35") (pinfunction "V+_35") (pintype "power_in"))
      (node (ref "IC58") (pin "35") (pinfunction "V+_35") (pintype "power_in"))
    )
    (net (code "258") (name "unconnected-(IC39-NC-Pad11)") (class "Default")
      (node (ref "IC39") (pin "11") (pinfunction "NC_11") (pintype "passive"))
    )
    (net (code "259") (name "unconnected-(IC39-NC-Pad20)") (class "Default")
      (node (ref "IC39") (pin "20") (pinfunction "NC_20") (pintype "passive"))
    )
    (net (code "260") (name "unconnected-(IC39-NC-Pad31)") (class "Default")
      (node (ref "IC39") (pin "31") (pinfunction "NC_31") (pintype "passive"))
    )
    (net (code "261") (name "unconnected-(IC39-P17-Pad10)") (class "Default")
      (node (ref "IC39") (pin "10") (pinfunction "P17_10") (pintype "bidirectional"))
    )
    (net (code "262") (name "unconnected-(IC47-NC-Pad11)") (class "Default")
      (node (ref "IC47") (pin "11") (pinfunction "NC_11") (pintype "passive"))
    )
    (net (code "263") (name "unconnected-(IC47-NC-Pad20)") (class "Default")
      (node (ref "IC47") (pin "20") (pinfunction "NC_20") (pintype "passive"))
    )
    (net (code "264") (name "unconnected-(IC47-NC-Pad31)") (class "Default")
      (node (ref "IC47") (pin "31") (pinfunction "NC_31") (pintype "passive"))
    )
    (net (code "265") (name "unconnected-(IC48-NC-Pad11)") (class "Default")
      (node (ref "IC48") (pin "11") (pinfunction "NC_11") (pintype "passive"))
    )
    (net (code "266") (name "unconnected-(IC48-NC-Pad20)") (class "Default")
      (node (ref "IC48") (pin "20") (pinfunction "NC_20") (pintype "passive"))
    )
    (net (code "267") (name "unconnected-(IC48-NC-Pad31)") (class "Default")
      (node (ref "IC48") (pin "31") (pinfunction "NC_31") (pintype "passive"))
    )
    (net (code "268") (name "unconnected-(IC49-NC-Pad11)") (class "Default")
      (node (ref "IC49") (pin "11") (pinfunction "NC_11") (pintype "passive"))
    )
    (net (code "269") (name "unconnected-(IC49-NC-Pad20)") (class "Default")
      (node (ref "IC49") (pin "20") (pinfunction "NC_20") (pintype "passive"))
    )
    (net (code "270") (name "unconnected-(IC49-NC-Pad31)") (class "Default")
      (node (ref "IC49") (pin "31") (pinfunction "NC_31") (pintype "passive"))
    )
    (net (code "271") (name "unconnected-(IC50-NC-Pad11)") (class "Default")
      (node (ref "IC50") (pin "11") (pinfunction "NC_11") (pintype "passive"))
    )
    (net (code "272") (name "unconnected-(IC50-NC-Pad20)") (class "Default")
      (node (ref "IC50") (pin "20") (pinfunction "NC_20") (pintype "passive"))
    )
    (net (code "273") (name "unconnected-(IC50-NC-Pad31)") (class "Default")
      (node (ref "IC50") (pin "31") (pinfunction "NC_31") (pintype "passive"))
    )
    (net (code "274") (name "unconnected-(IC58-NC-Pad11)") (class "Default")
      (node (ref "IC58") (pin "11") (pinfunction "NC_11") (pintype "passive"))
    )
    (net (code "275") (name "unconnected-(IC58-NC-Pad20)") (class "Default")
      (node (ref "IC58") (pin "20") (pinfunction "NC_20") (pintype "passive"))
    )
    (net (code "276") (name "unconnected-(IC58-NC-Pad31)") (class "Default")
      (node (ref "IC58") (pin "31") (pinfunction "NC_31") (pintype "passive"))
    )
    (net (code "277") (name "unconnected-(IC58-P15-Pad8)") (class "Default")
      (node (ref "IC58") (pin "8") (pinfunction "P15_8") (pintype "bidirectional"))
    )
    (net (code "278") (name "unconnected-(IC58-P16-Pad9)") (class "Default")
      (node (ref "IC58") (pin "9") (pinfunction "P16_9") (pintype "bidirectional"))
    )
    (net (code "279") (name "unconnected-(IC58-P17-Pad10)") (class "Default")
      (node (ref "IC58") (pin "10") (pinfunction "P17_10") (pintype "bidirectional"))
    )
  )
)
